# Power_Circuit.net
KiCad netlist of a schematic drawn in EAGLE
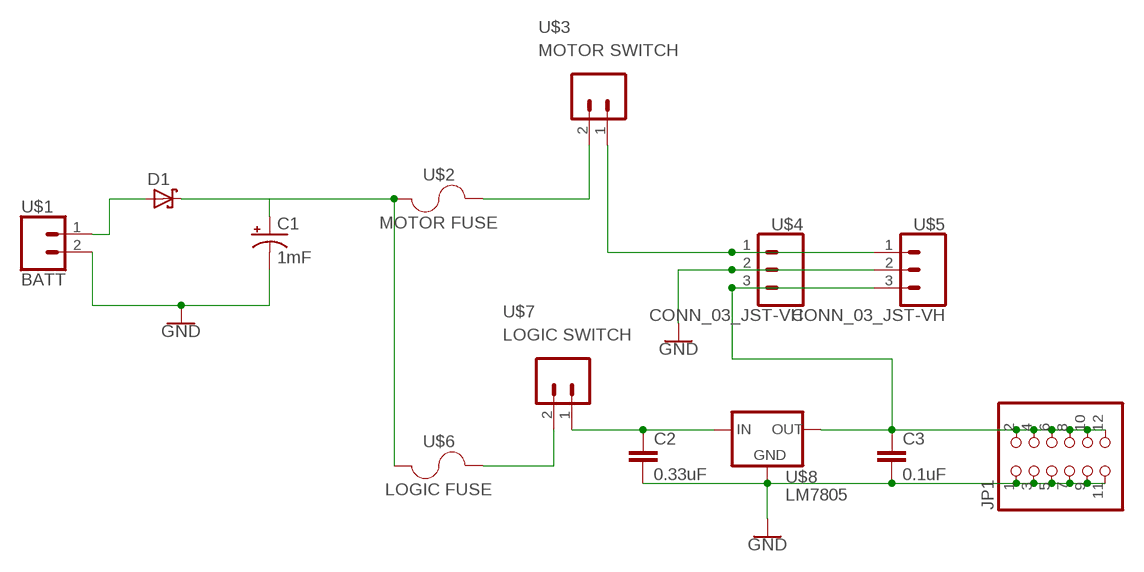
[diagram p0: schematic, sheet 1]

(export (version "E")
  (design (tool "Eeschema 10.0.6"))
  (components
    (comp (ref "C1")
      (value "1mF")
      (footprint "eagle-import:CPOL-RADIAL-5MM-10MM")
      (libsource (lib "eagle-import") (part "1000UF-RADIAL-5MM-25V-20%"))
    )
    (comp (ref "C2")
      (value "0.33uF")
      (footprint "eagle-import:C5B3")
      (libsource (lib "eagle-import") (part "C5/3"))
    )
    (comp (ref "C3")
      (value "0.1uF")
      (footprint "eagle-import:C5B3")
      (libsource (lib "eagle-import") (part "C5/3"))
    )
    (comp (ref "D1")
      (value "SCHOTTKY-DIODEP6T15")
      (footprint "eagle-import:P6T15")
      (libsource (lib "eagle-import") (part "SCHOTTKY-DIODEP6T15"))
    )
    (comp (ref "JP1")
      (value "PINHD-2X6")
      (footprint "eagle-import:2X06")
      (libsource (lib "eagle-import") (part "PINHD-2X6"))
    )
    (comp (ref "U$1")
      (value "BATT")
      (footprint "eagle-import:B2P-VH")
      (libsource (lib "eagle-import") (part "CONN_02_JST-VH"))
    )
    (comp (ref "U$2")
      (value "MOTOR FUSE")
      (footprint "eagle-import:SL-1538")
      (libsource (lib "eagle-import") (part "FUSE_MINI_BLADE"))
    )
    (comp (ref "U$3")
      (value "MOTOR SWITCH")
      (footprint "eagle-import:B2P-VH")
      (libsource (lib "eagle-import") (part "CONN_02_JST-VH"))
    )
    (comp (ref "U$4")
      (value "CONN_03_JST-VH")
      (footprint "eagle-import:B3P-VH")
      (libsource (lib "eagle-import") (part "CONN_03_JST-VH"))
    )
    (comp (ref "U$5")
      (value "CONN_03_JST-VH")
      (footprint "eagle-import:B3P-VH")
      (libsource (lib "eagle-import") (part "CONN_03_JST-VH"))
    )
    (comp (ref "U$6")
      (value "LOGIC FUSE")
      (footprint "eagle-import:SL-1538")
      (libsource (lib "eagle-import") (part "FUSE_MINI_BLADE"))
    )
    (comp (ref "U$7")
      (value "LOGIC SWITCH")
      (footprint "eagle-import:B2P-VH")
      (libsource (lib "eagle-import") (part "CONN_02_JST-VH"))
    )
    (comp (ref "U$8")
      (value "LM7805")
      (footprint "eagle-import:TO220-ADJ")
      (libsource (lib "eagle-import") (part "LM7805"))
    )
  )
  (nets
    (net (code "1") (name "GND") (class "Default")
      (node (ref "C1") (pin "-") (pinfunction "-_-") (pintype "passive"))
      (node (ref "C2") (pin "2") (pinfunction "2_2") (pintype "passive"))
      (node (ref "C3") (pin "2") (pinfunction "2_2") (pintype "passive"))
      (node (ref "JP1") (pin "1") (pinfunction "1_1") (pintype "passive"))
      (node (ref "JP1") (pin "11") (pinfunction "11_11") (pintype "passive"))
      (node (ref "JP1") (pin "3") (pinfunction "3_3") (pintype "passive"))
      (node (ref "JP1") (pin "5") (pinfunction "5_5") (pintype "passive"))
      (node (ref "JP1") (pin "7") (pinfunction "7_7") (pintype "passive"))
      (node (ref "JP1") (pin "9") (pinfunction "9_9") (pintype "passive"))
      (node (ref "U$1") (pin "2") (pinfunction "2_2") (pintype "passive"))
      (node (ref "U$4") (pin "2") (pinfunction "2_2") (pintype "passive"))
      (node (ref "U$5") (pin "2") (pinfunction "2_2") (pintype "passive"))
      (node (ref "U$8") (pin "GND") (pinfunction "GND_GND") (pintype "input"))
    )
    (net (code "2") (name "Net-(D1-PadA)") (class "Default")
      (node (ref "D1") (pin "A") (pinfunction "A_A") (pintype "passive"))
      (node (ref "U$1") (pin "1") (pinfunction "1_1") (pintype "passive"))
    )
    (net (code "3") (name "Net-(U$2-1)") (class "Default")
      (node (ref "C1") (pin "+") (pinfunction "+_+") (pintype "passive"))
      (node (ref "D1") (pin "C") (pinfunction "C_C") (pintype "passive"))
      (node (ref "U$2") (pin "P$1") (pinfunction "1_P$1") (pintype "bidirectional"))
      (node (ref "U$6") (pin "P$1") (pinfunction "1_P$1") (pintype "bidirectional"))
    )
    (net (code "4") (name "Net-(U$2-2)") (class "Default")
      (node (ref "U$2") (pin "P$2") (pinfunction "2_P$2") (pintype "bidirectional"))
      (node (ref "U$3") (pin "2") (pinfunction "2_2") (pintype "passive"))
    )
    (net (code "5") (name "Net-(U$3-Pad1)") (class "Default")
      (node (ref "U$3") (pin "1") (pinfunction "1_1") (pintype "passive"))
      (node (ref "U$4") (pin "1") (pinfunction "1_1") (pintype "passive"))
      (node (ref "U$5") (pin "1") (pinfunction "1_1") (pintype "passive"))
    )
    (net (code "6") (name "Net-(U$6-2)") (class "Default")
      (node (ref "U$6") (pin "P$2") (pinfunction "2_P$2") (pintype "bidirectional"))
      (node (ref "U$7") (pin "2") (pinfunction "2_2") (pintype "passive"))
    )
    (net (code "7") (name "Net-(U$8-IN)") (class "Default")
      (node (ref "C2") (pin "1") (pinfunction "1_1") (pintype "passive"))
      (node (ref "U$7") (pin "1") (pinfunction "1_1") (pintype "passive"))
      (node (ref "U$8") (pin "INPUT") (pinfunction "IN_INPUT") (pintype "input"))
    )
    (net (code "8") (name "Net-(U$8-OUT)") (class "Default")
      (node (ref "C3") (pin "1") (pinfunction "1_1") (pintype "passive"))
      (node (ref "JP1") (pin "10") (pinfunction "10_10") (pintype "passive"))
      (node (ref "JP1") (pin "12") (pinfunction "12_12") (pintype "passive"))
      (node (ref "JP1") (pin "2") (pinfunction "2_2") (pintype "passive"))
      (node (ref "JP1") (pin "4") (pinfunction "4_4") (pintype "passive"))
      (node (ref "JP1") (pin "6") (pinfunction "6_6") (pintype "passive"))
      (node (ref "JP1") (pin "8") (pinfunction "8_8") (pintype "passive"))
      (node (ref "U$4") (pin "3") (pinfunction "3_3") (pintype "passive"))
      (node (ref "U$5") (pin "3") (pinfunction "3_3") (pintype "passive"))
      (node (ref "U$8") (pin "OUTPUT") (pinfunction "OUT_OUTPUT") (pintype "passive"))
    )
  )
)
